# adapter.net
KiCad netlist of a schematic drawn in EAGLE
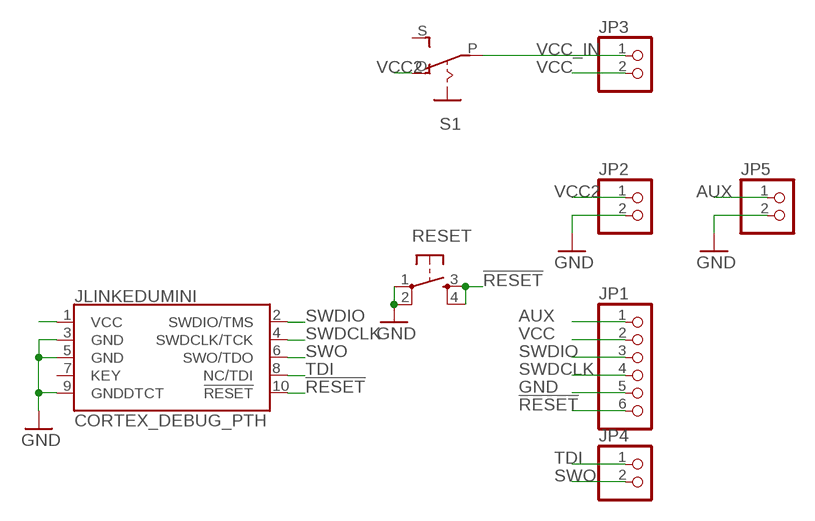
[diagram p0: schematic, sheet 1]

(export (version "E")
  (design (tool "Eeschema 10.0.6"))
  (components
    (comp (ref "JLINKEDUMINI")
      (value "CORTEX_DEBUG_PTH")
      (footprint "eagle-import:2X5-PTH-1.27MM")
      (libsource (lib "eagle-import") (part "CORTEX_DEBUG_PTH"))
    )
    (comp (ref "JP1")
      (value "PINHD-1X6")
      (footprint "eagle-import:1X06")
      (libsource (lib "eagle-import") (part "PINHD-1X6"))
    )
    (comp (ref "JP2")
      (value "PINHD-1X2")
      (footprint "eagle-import:1X02")
      (libsource (lib "eagle-import") (part "PINHD-1X2"))
    )
    (comp (ref "JP3")
      (value "PINHD-1X2")
      (footprint "eagle-import:1X02")
      (libsource (lib "eagle-import") (part "PINHD-1X2"))
    )
    (comp (ref "JP4")
      (value "PINHD-1X2")
      (footprint "eagle-import:1X02")
      (libsource (lib "eagle-import") (part "PINHD-1X2"))
    )
    (comp (ref "JP5")
      (value "PINHD-1X2")
      (footprint "eagle-import:1X02")
      (libsource (lib "eagle-import") (part "PINHD-1X2"))
    )
    (comp (ref "RESET")
      (value "TAC_SWITCHPTH")
      (footprint "eagle-import:TACTILE-PTH")
      (libsource (lib "eagle-import") (part "TAC_SWITCHPTH"))
    )
    (comp (ref "S1")
      (value "S-ON-ON")
      (footprint "eagle-import:ES_100SP1T6B11M2QEH")
      (libsource (lib "eagle-import") (part "S-ON-ON"))
    )
  )
  (nets
    (net (code "1") (name "/AUX") (class "Default")
      (node (ref "JP1") (pin "1") (pinfunction "1_1") (pintype "passive"))
      (node (ref "JP5") (pin "1") (pinfunction "1_1") (pintype "passive"))
    )
    (net (code "2") (name "/SWDCLK") (class "Default")
      (node (ref "JLINKEDUMINI") (pin "4") (pinfunction "SWDCLK/TCK_4") (pintype "bidirectional"))
      (node (ref "JP1") (pin "4") (pinfunction "4_4") (pintype "passive"))
    )
    (net (code "3") (name "/SWDIO") (class "Default")
      (node (ref "JLINKEDUMINI") (pin "2") (pinfunction "SWDIO/TMS_2") (pintype "bidirectional"))
      (node (ref "JP1") (pin "3") (pinfunction "3_3") (pintype "passive"))
    )
    (net (code "4") (name "/SWO") (class "Default")
      (node (ref "JLINKEDUMINI") (pin "6") (pinfunction "SWO/TDO_6") (pintype "bidirectional"))
      (node (ref "JP4") (pin "2") (pinfunction "2_2") (pintype "passive"))
    )
    (net (code "5") (name "/TDI") (class "Default")
      (node (ref "JLINKEDUMINI") (pin "8") (pinfunction "NC/TDI_8") (pintype "bidirectional"))
      (node (ref "JP4") (pin "1") (pinfunction "1_1") (pintype "passive"))
    )
    (net (code "6") (name "/VCC") (class "Default")
      (node (ref "JLINKEDUMINI") (pin "1") (pinfunction "VCC_1") (pintype "bidirectional"))
      (node (ref "JP1") (pin "2") (pinfunction "2_2") (pintype "passive"))
      (node (ref "JP3") (pin "2") (pinfunction "2_2") (pintype "passive"))
    )
    (net (code "7") (name "/VCC2") (class "Default")
      (node (ref "JP2") (pin "1") (pinfunction "1_1") (pintype "passive"))
      (node (ref "S1") (pin "O") (pinfunction "O_O") (pintype "passive"))
    )
    (net (code "8") (name "/VCC_IN") (class "Default")
      (node (ref "JP3") (pin "1") (pinfunction "1_1") (pintype "passive"))
      (node (ref "S1") (pin "P") (pinfunction "P_P") (pintype "passive"))
    )
    (net (code "9") (name "/~{RESET}") (class "Default")
      (node (ref "JLINKEDUMINI") (pin "10") (pinfunction "~{RESET}_10") (pintype "bidirectional"))
      (node (ref "JP1") (pin "6") (pinfunction "6_6") (pintype "passive"))
      (node (ref "RESET") (pin "3") (pinfunction "3_3") (pintype "passive"))
      (node (ref "RESET") (pin "4") (pinfunction "4_4") (pintype "passive"))
    )
    (net (code "10") (name "GND") (class "Default")
      (node (ref "JLINKEDUMINI") (pin "3") (pinfunction "GND_3") (pintype "bidirectional"))
      (node (ref "JLINKEDUMINI") (pin "5") (pinfunction "GND_5") (pintype "bidirectional"))
      (node (ref "JLINKEDUMINI") (pin "9") (pinfunction "GNDDTCT_9") (pintype "bidirectional"))
      (node (ref "JP1") (pin "5") (pinfunction "5_5") (pintype "passive"))
      (node (ref "JP2") (pin "2") (pinfunction "2_2") (pintype "passive"))
      (node (ref "JP5") (pin "2") (pinfunction "2_2") (pintype "passive"))
      (node (ref "RESET") (pin "1") (pinfunction "1_1") (pintype "passive"))
      (node (ref "RESET") (pin "2") (pinfunction "2_2") (pintype "passive"))
    )
    (net (code "11") (name "unconnected-(JLINKEDUMINI-KEY-Pad7)") (class "Default")
      (node (ref "JLINKEDUMINI") (pin "7") (pinfunction "KEY_7") (pintype "bidirectional"))
    )
    (net (code "12") (name "unconnected-(S1-PadS)") (class "Default")
      (node (ref "S1") (pin "S") (pinfunction "S_S") (pintype "passive"))
    )
  )
)
